# ProPrj_Sierra_Wireless_M2_Carrier_2026-0.net
KiCad netlist of a schematic drawn in EasyEDA Pro
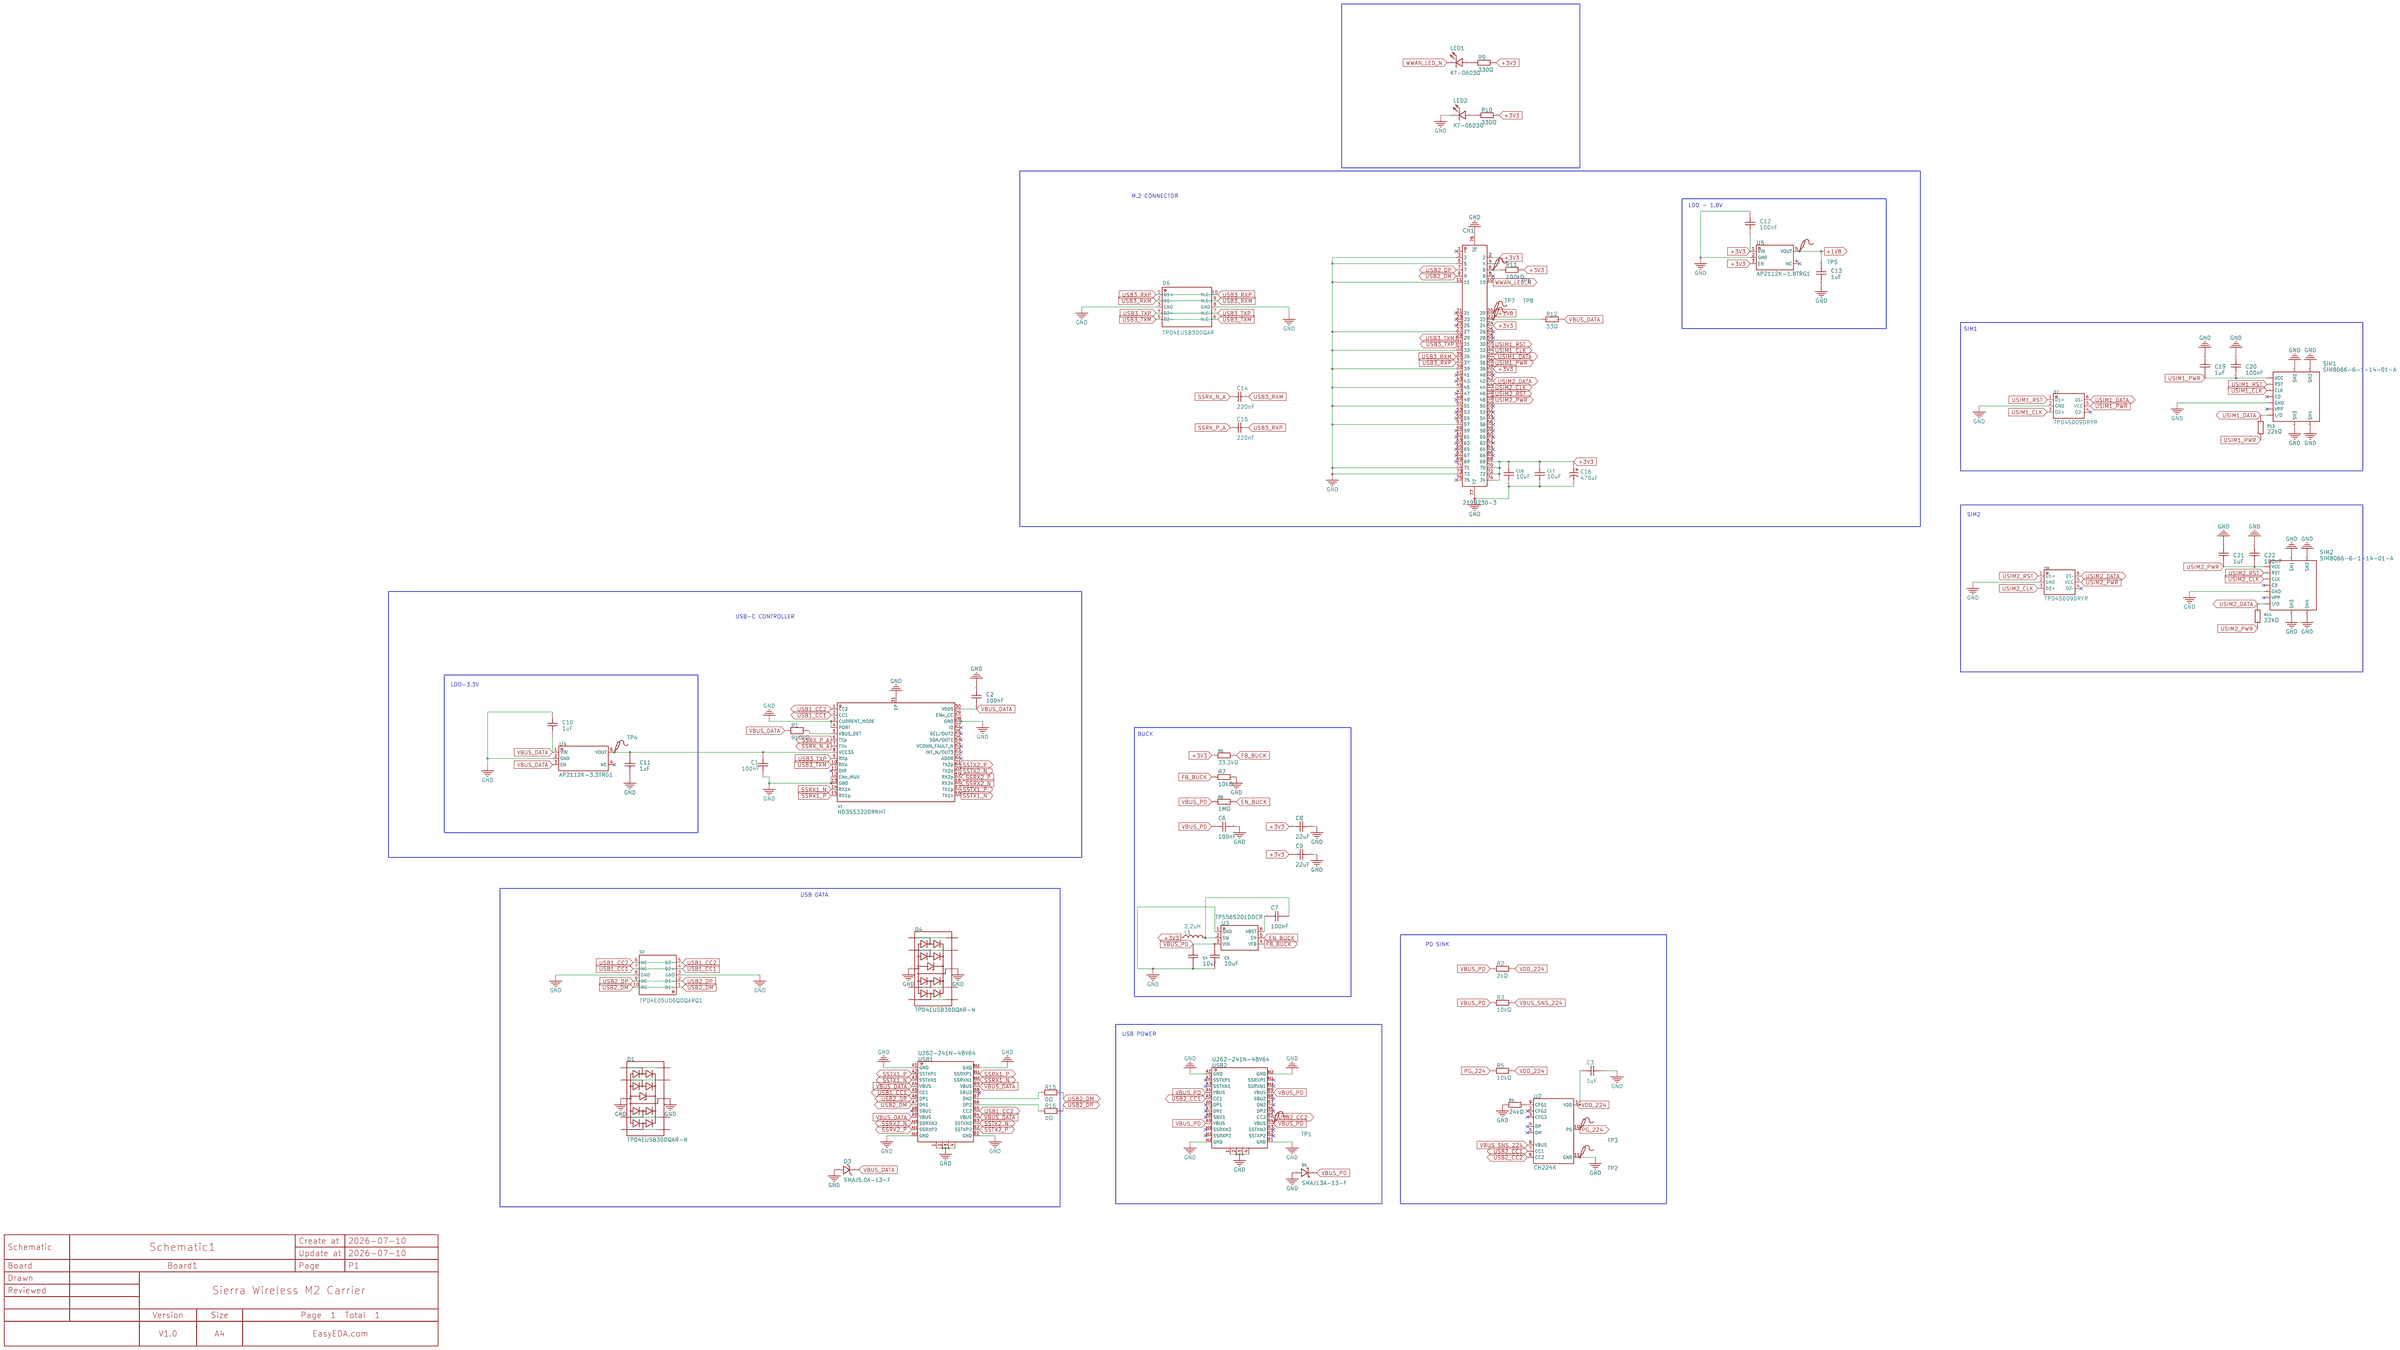
[diagram p0: schematic sheet]

(export (version "E")
  (design (tool "Eeschema 10.0.6"))
  (components
    (comp (ref "C1")
      (value "100nF")
      (footprint "easyedapro:C0603")
      (libsource (lib "easyedapro") (part "CAP"))
    )
    (comp (ref "C2")
      (value "100nF")
      (footprint "easyedapro:C0603")
      (libsource (lib "easyedapro") (part "CAP"))
    )
    (comp (ref "C3")
      (value "1uF")
      (footprint "easyedapro:C0603")
      (description "Capacitance:1uF Tolerance:±10% Tolerance:±10% Voltage Rating:50V Temperature Coefficient:X5R")
      (fields
        (field (name "Manufacturer Part") "CL10A105KB8NNNC")
        (field (name "Manufacturer") "SAMSUNG(三星)")
      )
      (libsource (lib "easyedapro") (part "CL10A105KB8NNNC"))
    )
    (comp (ref "C4")
      (value "10uF")
      (footprint "easyedapro:C0603")
      (description "Capacitance:10uF Tolerance:±20% Tolerance:±20% Voltage Rating:25V Temperature Coefficient:X5R")
      (fields
        (field (name "Manufacturer Part") "CL10A106MA8NRNC")
        (field (name "Manufacturer") "SAMSUNG(三星)")
      )
      (libsource (lib "easyedapro") (part "CL10A106MA8NRNC"))
    )
    (comp (ref "C5")
      (value "10uF")
      (footprint "easyedapro:C0603")
      (description "Capacitance:10uF Tolerance:±20% Tolerance:±20% Voltage Rating:25V Temperature Coefficient:X5R")
      (fields
        (field (name "Manufacturer Part") "CL10A106MA8NRNC")
        (field (name "Manufacturer") "SAMSUNG(三星)")
      )
      (libsource (lib "easyedapro") (part "CL10A106MA8NRNC"))
    )
    (comp (ref "C6")
      (value "100nF")
      (footprint "easyedapro:C0402")
      (description "Capacitance:100nF Tolerance:±10% Tolerance:±10% Voltage Rating:50V Temperature Coefficient:X7R")
      (fields
        (field (name "Manufacturer Part") "CL05B104KB54PNC")
        (field (name "Manufacturer") "SAMSUNG(三星)")
      )
      (libsource (lib "easyedapro") (part "CL05B104KB54PNC"))
    )
    (comp (ref "C7")
      (value "100nF")
      (footprint "easyedapro:C0402")
      (description "Capacitance:100nF Tolerance:±10% Tolerance:±10% Voltage Rating:50V Temperature Coefficient:X7R")
      (fields
        (field (name "Manufacturer Part") "CL05B104KB54PNC")
        (field (name "Manufacturer") "SAMSUNG(三星)")
      )
      (libsource (lib "easyedapro") (part "CL05B104KB54PNC"))
    )
    (comp (ref "C8")
      (value "22uF")
      (footprint "easyedapro:C0603")
      (description "Capacitance:22uF Tolerance:±20% Tolerance:±20% Voltage Rating:10V Temperature Coefficient:X5R")
      (fields
        (field (name "Manufacturer Part") "CL10A226MP8NUNE")
        (field (name "Manufacturer") "SAMSUNG(三星)")
      )
      (libsource (lib "easyedapro") (part "CL10A226MP8NUNE"))
    )
    (comp (ref "C9")
      (value "22uF")
      (footprint "easyedapro:C0603")
      (description "Capacitance:22uF Tolerance:±20% Tolerance:±20% Voltage Rating:10V Temperature Coefficient:X5R")
      (fields
        (field (name "Manufacturer Part") "CL10A226MP8NUNE")
        (field (name "Manufacturer") "SAMSUNG(三星)")
      )
      (libsource (lib "easyedapro") (part "CL10A226MP8NUNE"))
    )
    (comp (ref "C10")
      (value "1uF")
      (footprint "easyedapro:C0603")
      (description "Capacitance:1uF Tolerance:±10% Tolerance:±10% Voltage Rating:50V Temperature Coefficient:X5R")
      (fields
        (field (name "Manufacturer Part") "CL10A105KB8NNNC")
        (field (name "Manufacturer") "SAMSUNG(三星)")
      )
      (libsource (lib "easyedapro") (part "CL10A105KB8NNNC"))
    )
    (comp (ref "C11")
      (value "1uF")
      (footprint "easyedapro:C0603")
      (description "Capacitance:1uF Tolerance:±10% Tolerance:±10% Voltage Rating:50V Temperature Coefficient:X5R")
      (fields
        (field (name "Manufacturer Part") "CL10A105KB8NNNC")
        (field (name "Manufacturer") "SAMSUNG(三星)")
      )
      (libsource (lib "easyedapro") (part "CL10A105KB8NNNC"))
    )
    (comp (ref "C12")
      (value "100nF")
      (footprint "easyedapro:C0402")
      (description "Capacitance:100nF Tolerance:±10% Tolerance:±10% Voltage Rating:50V Temperature Coefficient:X7R")
      (fields
        (field (name "Manufacturer Part") "CL05B104KB54PNC")
        (field (name "Manufacturer") "SAMSUNG(三星)")
      )
      (libsource (lib "easyedapro") (part "CL05B104KB54PNC"))
    )
    (comp (ref "C13")
      (value "1uF")
      (footprint "easyedapro:C0603")
      (description "Capacitance:1uF Tolerance:±10% Tolerance:±10% Voltage Rating:50V Temperature Coefficient:X5R")
      (fields
        (field (name "Manufacturer Part") "CL10A105KB8NNNC")
        (field (name "Manufacturer") "SAMSUNG(三星)")
      )
      (libsource (lib "easyedapro") (part "CL10A105KB8NNNC"))
    )
    (comp (ref "C14")
      (value "220nF")
      (footprint "easyedapro:C0603")
      (description "Capacitance:220nF Tolerance:±10% Tolerance:±10% Voltage Rating:50V Temperature Coefficient:X7R")
      (fields
        (field (name "Manufacturer Part") "CL10B224KB8NNNC")
        (field (name "Manufacturer") "SAMSUNG(三星)")
      )
      (libsource (lib "easyedapro") (part "CL10B224KB8NNNC"))
    )
    (comp (ref "C15")
      (value "220nF")
      (footprint "easyedapro:C0603")
      (description "Capacitance:220nF Tolerance:±10% Tolerance:±10% Voltage Rating:50V Temperature Coefficient:X7R")
      (fields
        (field (name "Manufacturer Part") "CL10B224KB8NNNC")
        (field (name "Manufacturer") "SAMSUNG(三星)")
      )
      (libsource (lib "easyedapro") (part "CL10B224KB8NNNC"))
    )
    (comp (ref "C16")
      (value "470uF")
      (footprint "easyedapro:CAP-TH_BD8.0-P3.50-D0.5-FD")
      (fields
        (field (name "Manufacturer Part") "03EC0575")
        (field (name "Manufacturer") "KNSCHA(科尼盛)")
        (field (name "Tolerance") "±20%")
      )
      (libsource (lib "easyedapro") (part "03EC0575"))
    )
    (comp (ref "C17")
      (value "10uF")
      (footprint "easyedapro:C0603")
      (description "Capacitance:10uF Tolerance:±20% Tolerance:±20% Voltage Rating:25V Temperature Coefficient:X5R")
      (fields
        (field (name "Manufacturer Part") "CL10A106MA8NRNC")
        (field (name "Manufacturer") "SAMSUNG(三星)")
      )
      (libsource (lib "easyedapro") (part "CL10A106MA8NRNC"))
    )
    (comp (ref "C18")
      (value "10uF")
      (footprint "easyedapro:C0603")
      (description "Capacitance:10uF Tolerance:±20% Tolerance:±20% Voltage Rating:25V Temperature Coefficient:X5R")
      (fields
        (field (name "Manufacturer Part") "CL10A106MA8NRNC")
        (field (name "Manufacturer") "SAMSUNG(三星)")
      )
      (libsource (lib "easyedapro") (part "CL10A106MA8NRNC"))
    )
    (comp (ref "C19")
      (value "1uF")
      (footprint "easyedapro:C0603")
      (description "Capacitance:1uF Tolerance:±10% Tolerance:±10% Voltage Rating:50V Temperature Coefficient:X5R")
      (fields
        (field (name "Manufacturer Part") "CL10A105KB8NNNC")
        (field (name "Manufacturer") "SAMSUNG(三星)")
      )
      (libsource (lib "easyedapro") (part "CL10A105KB8NNNC"))
    )
    (comp (ref "C20")
      (value "100nF")
      (footprint "easyedapro:C0402")
      (description "Capacitance:100nF Tolerance:±10% Tolerance:±10% Voltage Rating:50V Temperature Coefficient:X7R")
      (fields
        (field (name "Manufacturer Part") "CL05B104KB54PNC")
        (field (name "Manufacturer") "SAMSUNG(三星)")
      )
      (libsource (lib "easyedapro") (part "CL05B104KB54PNC"))
    )
    (comp (ref "C21")
      (value "1uF")
      (footprint "easyedapro:C0603")
      (description "Capacitance:1uF Tolerance:±10% Tolerance:±10% Voltage Rating:50V Temperature Coefficient:X5R")
      (fields
        (field (name "Manufacturer Part") "CL10A105KB8NNNC")
        (field (name "Manufacturer") "SAMSUNG(三星)")
      )
      (libsource (lib "easyedapro") (part "CL10A105KB8NNNC"))
    )
    (comp (ref "C22")
      (value "100nF")
      (footprint "easyedapro:C0402")
      (description "Capacitance:100nF Tolerance:±10% Tolerance:±10% Voltage Rating:50V Temperature Coefficient:X7R")
      (fields
        (field (name "Manufacturer Part") "CL05B104KB54PNC")
        (field (name "Manufacturer") "SAMSUNG(三星)")
      )
      (libsource (lib "easyedapro") (part "CL05B104KB54PNC"))
    )
    (comp (ref "CN1")
      (value "2199230-3")
      (footprint "easyedapro:PCIE-SMD_2199230-3_1")
      (fields (field (name "Manufacturer") "TE Connectivity(泰科电子)"))
      (libsource (lib "easyedapro") (part "2199230-3"))
    )
    (comp (ref "D1")
      (value "TPD4EUSB30DQAR-N")
      (footprint "easyedapro:DFN-10_L2.5-W1.0-P0.50-BL-A")
      (fields (field (name "Manufacturer") "BORN(伯恩半导体)"))
      (libsource (lib "easyedapro") (part "TPD4EUSB30DQAR-N"))
    )
    (comp (ref "D2")
      (value "TPD4E05U06QDQARQ1")
      (footprint "easyedapro:USON-10_L2.5-W1.0-P0.50-BL")
      (fields (field (name "Manufacturer") "TI(德州仪器)"))
      (libsource (lib "easyedapro") (part "TPD4E05U06QDQARQ1"))
    )
    (comp (ref "D3")
      (value "SMAJ5.0A-13-F")
      (footprint "easyedapro:SMA_L4.3-W2.6-LS5.2-RD")
      (fields (field (name "Manufacturer") "DIODES(美台)"))
      (libsource (lib "easyedapro") (part "SMAJ5.0A-13-F"))
    )
    (comp (ref "D4")
      (value "TPD4EUSB30DQAR-N")
      (footprint "easyedapro:DFN-10_L2.5-W1.0-P0.50-BL-A")
      (fields (field (name "Manufacturer") "BORN(伯恩半导体)"))
      (libsource (lib "easyedapro") (part "TPD4EUSB30DQAR-N"))
    )
    (comp (ref "D5")
      (value "SMAJ13A-13-F")
      (footprint "easyedapro:SMA_L4.4-W2.6-LS5.0-RD")
      (fields (field (name "Manufacturer") "DIODES(美台)"))
      (libsource (lib "easyedapro") (part "SMAJ13A-13-F"))
    )
    (comp (ref "D6")
      (value "TPD4EUSB30DQAR")
      (footprint "easyedapro:USON-10_L2.5-W1.0-P0.50-BL")
      (fields (field (name "Manufacturer") "TI(德州仪器)"))
      (libsource (lib "easyedapro") (part "TPD4EUSB30DQAR"))
    )
    (comp (ref "D7")
      (value "TPD4S009DRYR")
      (footprint "easyedapro:SON-6_L1.5-W1.0-P0.50-TL")
      (fields (field (name "Manufacturer") "TI(德州仪器)"))
      (libsource (lib "easyedapro") (part "TPD4S009DRYR"))
    )
    (comp (ref "D8")
      (value "TPD4S009DRYR")
      (footprint "easyedapro:SON-6_L1.5-W1.0-P0.50-TL")
      (fields (field (name "Manufacturer") "TI(德州仪器)"))
      (libsource (lib "easyedapro") (part "TPD4S009DRYR"))
    )
    (comp (ref "L1")
      (value "2.2uH")
      (footprint "easyedapro:IND-SMD_L4.0-W4.0_YHNR4020")
      (fields (field (name "Manufacturer Part") "YHNR4020-2R2M") (field (name "Manufacturer") "YJYCOIN(益嘉源)"))
      (libsource (lib "easyedapro") (part "YHNR4020-2R2M"))
    )
    (comp (ref "LED1")
      (value "KT-0603G")
      (footprint "easyedapro:LED0603-RD")
      (fields (field (name "Manufacturer") "KENTO"))
      (libsource (lib "easyedapro") (part "0603 Green 509-620mcd"))
    )
    (comp (ref "LED2")
      (value "KT-0603G")
      (footprint "easyedapro:LED0603-RD")
      (fields (field (name "Manufacturer") "KENTO"))
      (libsource (lib "easyedapro") (part "0603 Green 509-620mcd"))
    )
    (comp (ref "R1")
      (value "910kΩ")
      (footprint "easyedapro:R0402")
      (fields
        (field (name "Manufacturer Part") "FRC0402F9103TS")
        (field (name "Manufacturer") "FOJAN(富捷)")
        (field (name "Tolerance") "±1%")
      )
      (libsource (lib "easyedapro") (part "FRC0402F9103TS"))
    )
    (comp (ref "R2")
      (value "2kΩ")
      (footprint "easyedapro:R0805")
      (fields
        (field (name "Manufacturer Part") "0805W8J0202T5E")
        (field (name "Manufacturer") "UNI-ROYAL(厚声)")
        (field (name "Tolerance") "±5%")
      )
      (libsource (lib "easyedapro") (part "0805W8J0202T5E"))
    )
    (comp (ref "R3")
      (value "10kΩ")
      (footprint "easyedapro:R0603")
      (fields
        (field (name "Manufacturer Part") "RC0603FR-0710KL")
        (field (name "Manufacturer") "YAGEO(国巨)")
        (field (name "Tolerance") "±1%")
      )
      (libsource (lib "easyedapro") (part "RC0603FR-0710KL"))
    )
    (comp (ref "R4")
      (value "24kΩ")
      (footprint "easyedapro:R0603")
      (fields
        (field (name "Manufacturer Part") "0603WAF2402T5E")
        (field (name "Manufacturer") "UNI-ROYAL(厚声)")
        (field (name "Tolerance") "±1%")
      )
      (libsource (lib "easyedapro") (part "0603WAF2402T5E"))
    )
    (comp (ref "R5")
      (value "10kΩ")
      (footprint "easyedapro:R0603")
      (fields
        (field (name "Manufacturer Part") "RC0603FR-0710KL")
        (field (name "Manufacturer") "YAGEO(国巨)")
        (field (name "Tolerance") "±1%")
      )
      (libsource (lib "easyedapro") (part "RC0603FR-0710KL"))
    )
    (comp (ref "R6")
      (value "33.2kΩ")
      (footprint "easyedapro:R0603")
      (fields
        (field (name "Manufacturer Part") "RMC060333.2K1%N")
        (field (name "Manufacturer") "Tyohm(幸亚电阻)")
        (field (name "Tolerance") "±1%")
      )
      (libsource (lib "easyedapro") (part "RMC060333.2K1%N"))
    )
    (comp (ref "R7")
      (value "10kΩ")
      (footprint "easyedapro:R0603")
      (fields
        (field (name "Manufacturer Part") "RC0603FR-0710KL")
        (field (name "Manufacturer") "YAGEO(国巨)")
        (field (name "Tolerance") "±1%")
      )
      (libsource (lib "easyedapro") (part "RC0603FR-0710KL"))
    )
    (comp (ref "R8")
      (value "1MΩ")
      (footprint "easyedapro:R0603")
      (fields
        (field (name "Manufacturer Part") "0603WAF1004T5E")
        (field (name "Manufacturer") "UNI-ROYAL(厚声)")
        (field (name "Tolerance") "±1%")
      )
      (libsource (lib "easyedapro") (part "0603WAF1004T5E"))
    )
    (comp (ref "R9")
      (value "330Ω")
      (footprint "easyedapro:R0603")
      (fields
        (field (name "Manufacturer Part") "0603WAF3300T5E")
        (field (name "Manufacturer") "UNI-ROYAL(厚声)")
        (field (name "Tolerance") "±1%")
      )
      (libsource (lib "easyedapro") (part "0603WAF3300T5E"))
    )
    (comp (ref "R10")
      (value "330Ω")
      (footprint "easyedapro:R0603")
      (fields
        (field (name "Manufacturer Part") "0603WAF3300T5E")
        (field (name "Manufacturer") "UNI-ROYAL(厚声)")
        (field (name "Tolerance") "±1%")
      )
      (libsource (lib "easyedapro") (part "0603WAF3300T5E"))
    )
    (comp (ref "R11")
      (value "100kΩ")
      (footprint "easyedapro:R0603")
      (fields
        (field (name "Manufacturer Part") "0603WAF1003T5E")
        (field (name "Manufacturer") "UNI-ROYAL(厚声)")
        (field (name "Tolerance") "±1%")
      )
      (libsource (lib "easyedapro") (part "0603WAF1003T5E"))
    )
    (comp (ref "R12")
      (value "33Ω")
      (footprint "easyedapro:R0603")
      (fields
        (field (name "Manufacturer Part") "0603WAF330JT5E")
        (field (name "Manufacturer") "UNI-ROYAL(厚声)")
        (field (name "Tolerance") "±1%")
      )
      (libsource (lib "easyedapro") (part "0603WAF330JT5E"))
    )
    (comp (ref "R13")
      (value "22kΩ")
      (footprint "easyedapro:R0603")
      (fields
        (field (name "Manufacturer Part") "0603WAF2202T5E")
        (field (name "Manufacturer") "UNI-ROYAL(厚声)")
        (field (name "Tolerance") "±1%")
      )
      (libsource (lib "easyedapro") (part "0603WAF2202T5E"))
    )
    (comp (ref "R14")
      (value "22kΩ")
      (footprint "easyedapro:R0603")
      (fields
        (field (name "Manufacturer Part") "0603WAF2202T5E")
        (field (name "Manufacturer") "UNI-ROYAL(厚声)")
        (field (name "Tolerance") "±1%")
      )
      (libsource (lib "easyedapro") (part "0603WAF2202T5E"))
    )
    (comp (ref "R15")
      (value "0Ω")
      (footprint "easyedapro:R0603")
      (fields
        (field (name "Manufacturer Part") "RC0603JR-070RL")
        (field (name "Manufacturer") "YAGEO(国巨)")
        (field (name "Tolerance") "±5%")
      )
      (libsource (lib "easyedapro") (part "RC0603JR-070RL"))
    )
    (comp (ref "R16")
      (value "0Ω")
      (footprint "easyedapro:R0603")
      (fields
        (field (name "Manufacturer Part") "RC0603JR-070RL")
        (field (name "Manufacturer") "YAGEO(国巨)")
        (field (name "Tolerance") "±5%")
      )
      (libsource (lib "easyedapro") (part "RC0603JR-070RL"))
    )
    (comp (ref "SIM1")
      (value "SIM8066-6-1-14-01-A")
      (footprint "easyedapro:SIM-SMD_SIM8066-6-1-14-01-A")
      (fields (field (name "Manufacturer") "GCT"))
      (libsource (lib "easyedapro") (part "SIM8066-6-1-14-01-A"))
    )
    (comp (ref "SIM2")
      (value "SIM8066-6-1-14-01-A")
      (footprint "easyedapro:SIM-SMD_SIM8066-6-1-14-01-A")
      (fields (field (name "Manufacturer") "GCT"))
      (libsource (lib "easyedapro") (part "SIM8066-6-1-14-01-A"))
    )
    (comp (ref "TP1")
      (value "~")
      (footprint "easyedapro:Test-Point-0.5mm")
      (libsource (lib "easyedapro") (part "Test-Point"))
    )
    (comp (ref "TP2")
      (value "~")
      (footprint "easyedapro:Test-Point-0.5mm")
      (libsource (lib "easyedapro") (part "Test-Point"))
    )
    (comp (ref "TP3")
      (value "~")
      (footprint "easyedapro:Test-Point-0.5mm")
      (libsource (lib "easyedapro") (part "Test-Point"))
    )
    (comp (ref "TP4")
      (value "~")
      (footprint "easyedapro:Test-Point-0.5mm")
      (libsource (lib "easyedapro") (part "Test-Point"))
    )
    (comp (ref "TP5")
      (value "~")
      (footprint "easyedapro:Test-Point-0.5mm")
      (description "Test Point 测试点")
      (libsource (lib "easyedapro") (part "Test-Point"))
    )
    (comp (ref "TP6")
      (value "~")
      (footprint "easyedapro:Test-Point-0.5mm")
      (libsource (lib "easyedapro") (part "Test-Point"))
    )
    (comp (ref "TP7")
      (value "~")
      (footprint "easyedapro:Test-Point-0.5mm")
      (libsource (lib "easyedapro") (part "Test-Point"))
    )
    (comp (ref "TP8")
      (value "~")
      (footprint "easyedapro:Test-Point-0.5mm")
      (libsource (lib "easyedapro") (part "Test-Point"))
    )
    (comp (ref "U1")
      (value "HD3SS3220RNHT")
      (footprint "easyedapro:WQFN-30_L4.5-W2.5-P0.4-BL-EP")
      (fields (field (name "Manufacturer") "TI(德州仪器)"))
      (libsource (lib "easyedapro") (part "HD3SS3220RNHT"))
    )
    (comp (ref "U2")
      (value "CH224K")
      (footprint "easyedapro:ESSOP-10_L4.9-W3.9-P1.0-LS6.0-TL-EP")
      (fields (field (name "Manufacturer") "WCH(南京沁恒)"))
      (libsource (lib "easyedapro") (part "CH224K"))
    )
    (comp (ref "U3")
      (value "TPS565201DDCR")
      (footprint "easyedapro:SOT-23-6_L2.9-W1.6-P0.95-LS2.8-BR")
      (fields (field (name "Manufacturer") "TI(德州仪器)"))
      (libsource (lib "easyedapro") (part "TPS565201DDCR"))
    )
    (comp (ref "U4")
      (value "AP2112K-3.3TRG1")
      (footprint "easyedapro:SOT-25-5_L2.9-W1.6-P0.95-LS2.8-BL")
      (fields (field (name "Manufacturer") "DIODES(美台)"))
      (libsource (lib "easyedapro") (part "AP2112K-3.3TRG1"))
    )
    (comp (ref "U5")
      (value "AP2112K-1.8TRG1")
      (footprint "easyedapro:SOT-25_L3.0-W1.6-P0.95-LS2.8-BL")
      (fields (field (name "Manufacturer") "DIODES(美台)"))
      (libsource (lib "easyedapro") (part "AP2112K-1.8TRG1"))
    )
    (comp (ref "USB1")
      (value "U262-241N-4BV64")
      (footprint "easyedapro:USB-C-SMD_TYC-324G")
      (fields (field (name "Manufacturer") "XKB Connection(中国星坤)"))
      (libsource (lib "easyedapro") (part "U262-241N-4BV64"))
    )
    (comp (ref "USB2")
      (value "U262-241N-4BV64")
      (footprint "easyedapro:USB-C-SMD_TYC-324G")
      (fields (field (name "Manufacturer") "XKB Connection(中国星坤)"))
      (libsource (lib "easyedapro") (part "U262-241N-4BV64"))
    )
  )
  (nets
    (net (code "1") (name "+1V8") (class "Default")
      (node (ref "C13") (pin "2") (pinfunction "2_2") (pintype "unspecified"))
      (node (ref "CN1") (pin "20") (pinfunction "20_20") (pintype "unspecified"))
      (node (ref "TP5") (pin "1") (pinfunction "1_1") (pintype "unspecified"))
      (node (ref "TP7") (pin "1") (pinfunction "1_1") (pintype "unspecified"))
      (node (ref "U5") (pin "5") (pinfunction "VOUT_5") (pintype "unspecified"))
    )
    (net (code "2") (name "+3V3") (class "Default")
      (node (ref "C12") (pin "1") (pinfunction "1_1") (pintype "input"))
      (node (ref "C16") (pin "1") (pinfunction "1_1") (pintype "input"))
      (node (ref "C17") (pin "1") (pinfunction "1_1") (pintype "input"))
      (node (ref "C18") (pin "1") (pinfunction "1_1") (pintype "input"))
      (node (ref "C8") (pin "1") (pinfunction "1_1") (pintype "unspecified"))
      (node (ref "C9") (pin "1") (pinfunction "1_1") (pintype "unspecified"))
      (node (ref "CN1") (pin "2") (pinfunction "2_2") (pintype "unspecified"))
      (node (ref "CN1") (pin "24") (pinfunction "24_24") (pintype "unspecified"))
      (node (ref "CN1") (pin "38") (pinfunction "38_38") (pintype "unspecified"))
      (node (ref "CN1") (pin "4") (pinfunction "4_4") (pintype "unspecified"))
      (node (ref "CN1") (pin "68") (pinfunction "68_68") (pintype "unspecified"))
      (node (ref "CN1") (pin "70") (pinfunction "70_70") (pintype "unspecified"))
      (node (ref "CN1") (pin "72") (pinfunction "72_72") (pintype "unspecified"))
      (node (ref "CN1") (pin "74") (pinfunction "74_74") (pintype "unspecified"))
      (node (ref "L1") (pin "1") (pinfunction "1_1") (pintype "unspecified"))
      (node (ref "R10") (pin "1") (pinfunction "1_1") (pintype "input"))
      (node (ref "R11") (pin "2") (pinfunction "2_2") (pintype "input"))
      (node (ref "R6") (pin "1") (pinfunction "1_1") (pintype "input"))
      (node (ref "R9") (pin "1") (pinfunction "1_1") (pintype "input"))
      (node (ref "U5") (pin "1") (pinfunction "VIN_1") (pintype "unspecified"))
      (node (ref "U5") (pin "3") (pinfunction "EN_3") (pintype "unspecified"))
    )
    (net (code "3") (name "EN_BUCK") (class "Default")
      (node (ref "R8") (pin "2") (pinfunction "2_2") (pintype "input"))
      (node (ref "U3") (pin "5") (pinfunction "EN_5") (pintype "unspecified"))
    )
    (net (code "4") (name "FB_BUCK") (class "Default")
      (node (ref "R6") (pin "2") (pinfunction "2_2") (pintype "input"))
      (node (ref "R7") (pin "1") (pinfunction "1_1") (pintype "input"))
      (node (ref "U3") (pin "4") (pinfunction "VFB_4") (pintype "unspecified"))
    )
    (net (code "5") (name "GND") (class "Default")
      (node (ref "C1") (pin "1") (pinfunction "1_1") (pintype "input"))
      (node (ref "C10") (pin "2") (pinfunction "2_2") (pintype "unspecified"))
      (node (ref "C11") (pin "1") (pinfunction "1_1") (pintype "unspecified"))
      (node (ref "C12") (pin "2") (pinfunction "2_2") (pintype "input"))
      (node (ref "C13") (pin "1") (pinfunction "1_1") (pintype "unspecified"))
      (node (ref "C16") (pin "2") (pinfunction "2_2") (pintype "input"))
      (node (ref "C17") (pin "2") (pinfunction "2_2") (pintype "input"))
      (node (ref "C18") (pin "2") (pinfunction "2_2") (pintype "input"))
      (node (ref "C19") (pin "1") (pinfunction "1_1") (pintype "unspecified"))
      (node (ref "C2") (pin "2") (pinfunction "2_2") (pintype "input"))
      (node (ref "C20") (pin "1") (pinfunction "1_1") (pintype "input"))
      (node (ref "C21") (pin "1") (pinfunction "1_1") (pintype "unspecified"))
      (node (ref "C22") (pin "1") (pinfunction "1_1") (pintype "input"))
      (node (ref "C3") (pin "2") (pinfunction "2_2") (pintype "unspecified"))
      (node (ref "C4") (pin "2") (pinfunction "2_2") (pintype "input"))
      (node (ref "C5") (pin "2") (pinfunction "2_2") (pintype "input"))
      (node (ref "C6") (pin "2") (pinfunction "2_2") (pintype "input"))
      (node (ref "C8") (pin "2") (pinfunction "2_2") (pintype "unspecified"))
      (node (ref "C9") (pin "2") (pinfunction "2_2") (pintype "unspecified"))
      (node (ref "CN1") (pin "11") (pinfunction "11_11") (pintype "unspecified"))
      (node (ref "CN1") (pin "27") (pinfunction "27_27") (pintype "unspecified"))
      (node (ref "CN1") (pin "3") (pinfunction "3_3") (pintype "unspecified"))
      (node (ref "CN1") (pin "33") (pinfunction "33_33") (pintype "unspecified"))
      (node (ref "CN1") (pin "39") (pinfunction "39_39") (pintype "unspecified"))
      (node (ref "CN1") (pin "45") (pinfunction "45_45") (pintype "unspecified"))
      (node (ref "CN1") (pin "5") (pinfunction "5_5") (pintype "unspecified"))
      (node (ref "CN1") (pin "51") (pinfunction "51_51") (pintype "unspecified"))
      (node (ref "CN1") (pin "57") (pinfunction "57_57") (pintype "unspecified"))
      (node (ref "CN1") (pin "71") (pinfunction "71_71") (pintype "unspecified"))
      (node (ref "CN1") (pin "73") (pinfunction "73_73") (pintype "unspecified"))
      (node (ref "CN1") (pin "76") (pinfunction "76_76") (pintype "unspecified"))
      (node (ref "CN1") (pin "77") (pinfunction "77_77") (pintype "unspecified"))
      (node (ref "D1") (pin "3") (pinfunction "3_3") (pintype "unspecified"))
      (node (ref "D1") (pin "8") (pinfunction "8_8") (pintype "unspecified"))
      (node (ref "D2") (pin "3") (pinfunction "GND_3") (pintype "input"))
      (node (ref "D2") (pin "8") (pinfunction "GND_8") (pintype "input"))
      (node (ref "D3") (pin "2") (pinfunction "A_2") (pintype "unspecified"))
      (node (ref "D4") (pin "3") (pinfunction "3_3") (pintype "unspecified"))
      (node (ref "D4") (pin "8") (pinfunction "8_8") (pintype "unspecified"))
      (node (ref "D5") (pin "2") (pinfunction "A_2") (pintype "input"))
      (node (ref "D6") (pin "3") (pinfunction "GND_3") (pintype "unspecified"))
      (node (ref "D6") (pin "8") (pinfunction "GND_8") (pintype "unspecified"))
      (node (ref "D7") (pin "2") (pinfunction "GND_2") (pintype "input"))
      (node (ref "D8") (pin "2") (pinfunction "GND_2") (pintype "input"))
      (node (ref "LED2") (pin "1") (pinfunction "K_1") (pintype "unspecified"))
      (node (ref "R4") (pin "1") (pinfunction "1_1") (pintype "input"))
      (node (ref "R7") (pin "2") (pinfunction "2_2") (pintype "input"))
      (node (ref "SIM1") (pin "5") (pinfunction "GND_5") (pintype "unspecified"))
      (node (ref "SIM1") (pin "SH1") (pinfunction "SH1_SH1") (pintype "unspecified"))
      (node (ref "SIM1") (pin "SH2") (pinfunction "SH2_SH2") (pintype "unspecified"))
      (node (ref "SIM1") (pin "SH3") (pinfunction "SH3_SH3") (pintype "unspecified"))
      (node (ref "SIM1") (pin "SH4") (pinfunction "SH4_SH4") (pintype "unspecified"))
      (node (ref "SIM2") (pin "5") (pinfunction "GND_5") (pintype "unspecified"))
      (node (ref "SIM2") (pin "SH1") (pinfunction "SH1_SH1") (pintype "unspecified"))
      (node (ref "SIM2") (pin "SH2") (pinfunction "SH2_SH2") (pintype "unspecified"))
      (node (ref "SIM2") (pin "SH3") (pinfunction "SH3_SH3") (pintype "unspecified"))
      (node (ref "SIM2") (pin "SH4") (pinfunction "SH4_SH4") (pintype "unspecified"))
      (node (ref "TP2") (pin "1") (pinfunction "1_1") (pintype "unspecified"))
      (node (ref "U1") (pin "12") (pinfunction "ENn_MUX_12") (pintype "input"))
      (node (ref "U1") (pin "13") (pinfunction "GND_13") (pintype "input"))
      (node (ref "U1") (pin "28") (pinfunction "GND_28") (pintype "input"))
      (node (ref "U1") (pin "29") (pinfunction "ENn_CC_29") (pintype "input"))
      (node (ref "U1") (pin "3") (pinfunction "CURRENT_MODE_3") (pintype "input"))
      (node (ref "U1") (pin "31") (pinfunction "EP_31") (pintype "input"))
      (node (ref "U1") (pin "4") (pinfunction "PORT_4") (pintype "input"))
      (node (ref "U2") (pin "11") (pinfunction "GND_11") (pintype "unspecified"))
      (node (ref "U3") (pin "1") (pinfunction "GND_1") (pintype "unspecified"))
      (node (ref "U4") (pin "2") (pinfunction "GND_2") (pintype "unspecified"))
      (node (ref "U5") (pin "2") (pinfunction "GND_2") (pintype "unspecified"))
      (node (ref "USB1") (pin "1") (pinfunction "1_1") (pintype "unspecified"))
      (node (ref "USB1") (pin "2") (pinfunction "2_2") (pintype "unspecified"))
      (node (ref "USB1") (pin "3") (pinfunction "3_3") (pintype "unspecified"))
      (node (ref "USB1") (pin "4") (pinfunction "4_4") (pintype "unspecified"))
      (node (ref "USB1") (pin "A1") (pinfunction "GND_A1") (pintype "unspecified"))
      (node (ref "USB1") (pin "A12") (pinfunction "GND_A12") (pintype "unspecified"))
      (node (ref "USB1") (pin "B1") (pinfunction "GND_B1") (pintype "unspecified"))
      (node (ref "USB1") (pin "B12") (pinfunction "GND_B12") (pintype "unspecified"))
      (node (ref "USB2") (pin "1") (pinfunction "1_1") (pintype "unspecified"))
      (node (ref "USB2") (pin "2") (pinfunction "2_2") (pintype "unspecified"))
      (node (ref "USB2") (pin "3") (pinfunction "3_3") (pintype "unspecified"))
      (node (ref "USB2") (pin "4") (pinfunction "4_4") (pintype "unspecified"))
      (node (ref "USB2") (pin "A1") (pinfunction "GND_A1") (pintype "unspecified"))
      (node (ref "USB2") (pin "A12") (pinfunction "GND_A12") (pintype "unspecified"))
      (node (ref "USB2") (pin "B1") (pinfunction "GND_B1") (pintype "unspecified"))
      (node (ref "USB2") (pin "B12") (pinfunction "GND_B12") (pintype "unspecified"))
    )
    (net (code "6") (name "Net-(CN1-Pad6)") (class "Default")
      (node (ref "CN1") (pin "6") (pinfunction "6_6") (pintype "unspecified"))
      (node (ref "R11") (pin "1") (pinfunction "1_1") (pintype "input"))
      (node (ref "TP6") (pin "1") (pinfunction "1_1") (pintype "unspecified"))
    )
    (net (code "7") (name "Net-(CN1-Pad22)") (class "Default")
      (node (ref "CN1") (pin "22") (pinfunction "22_22") (pintype "unspecified"))
      (node (ref "R12") (pin "1") (pinfunction "1_1") (pintype "input"))
      (node (ref "TP8") (pin "1") (pinfunction "1_1") (pintype "unspecified"))
    )
    (net (code "8") (name "Net-(D1-Pad1)") (class "Default")
      (node (ref "D1") (pin "1") (pinfunction "1_1") (pintype "unspecified"))
      (node (ref "D1") (pin "10") (pinfunction "10_10") (pintype "unspecified"))
    )
    (net (code "9") (name "Net-(D1-Pad2)") (class "Default")
      (node (ref "D1") (pin "2") (pinfunction "2_2") (pintype "unspecified"))
      (node (ref "D1") (pin "9") (pinfunction "9_9") (pintype "unspecified"))
    )
    (net (code "10") (name "Net-(D1-Pad4)") (class "Default")
      (node (ref "D1") (pin "4") (pinfunction "4_4") (pintype "unspecified"))
      (node (ref "D1") (pin "7") (pinfunction "7_7") (pintype "unspecified"))
    )
    (net (code "11") (name "Net-(D1-Pad5)") (class "Default")
      (node (ref "D1") (pin "5") (pinfunction "5_5") (pintype "unspecified"))
      (node (ref "D1") (pin "6") (pinfunction "6_6") (pintype "unspecified"))
    )
    (net (code "12") (name "Net-(D4-Pad1)") (class "Default")
      (node (ref "D4") (pin "1") (pinfunction "1_1") (pintype "unspecified"))
      (node (ref "D4") (pin "10") (pinfunction "10_10") (pintype "unspecified"))
    )
    (net (code "13") (name "Net-(D4-Pad2)") (class "Default")
      (node (ref "D4") (pin "2") (pinfunction "2_2") (pintype "unspecified"))
      (node (ref "D4") (pin "9") (pinfunction "9_9") (pintype "unspecified"))
    )
    (net (code "14") (name "Net-(D4-Pad4)") (class "Default")
      (node (ref "D4") (pin "4") (pinfunction "4_4") (pintype "unspecified"))
      (node (ref "D4") (pin "7") (pinfunction "7_7") (pintype "unspecified"))
    )
    (net (code "15") (name "Net-(D4-Pad5)") (class "Default")
      (node (ref "D4") (pin "5") (pinfunction "5_5") (pintype "unspecified"))
      (node (ref "D4") (pin "6") (pinfunction "6_6") (pintype "unspecified"))
    )
    (net (code "16") (name "Net-(LED1-A)") (class "Default")
      (node (ref "LED1") (pin "2") (pinfunction "A_2") (pintype "unspecified"))
      (node (ref "R9") (pin "2") (pinfunction "2_2") (pintype "input"))
    )
    (net (code "17") (name "Net-(LED2-A)") (class "Default")
      (node (ref "LED2") (pin "2") (pinfunction "A_2") (pintype "unspecified"))
      (node (ref "R10") (pin "2") (pinfunction "2_2") (pintype "input"))
    )
    (net (code "18") (name "Net-(U1-VBUS_DET)") (class "Default")
      (node (ref "R1") (pin "2") (pinfunction "2_2") (pintype "unspecified"))
      (node (ref "U1") (pin "5") (pinfunction "VBUS_DET_5") (pintype "input"))
    )
    (net (code "19") (name "Net-(U1-VCC33)") (class "Default")
      (node (ref "C1") (pin "2") (pinfunction "2_2") (pintype "input"))
      (node (ref "C11") (pin "2") (pinfunction "2_2") (pintype "unspecified"))
      (node (ref "TP4") (pin "1") (pinfunction "1_1") (pintype "unspecified"))
      (node (ref "U1") (pin "8") (pinfunction "VCC33_8") (pintype "input"))
      (node (ref "U4") (pin "5") (pinfunction "VOUT_5") (pintype "unspecified"))
    )
    (net (code "20") (name "Net-(U2-CFG1)") (class "Default")
      (node (ref "R4") (pin "2") (pinfunction "2_2") (pintype "input"))
      (node (ref "U2") (pin "9") (pinfunction "CFG1_9") (pintype "unspecified"))
    )
    (net (code "21") (name "Net-(U3-SW)") (class "Default")
      (node (ref "C7") (pin "1") (pinfunction "1_1") (pintype "input"))
      (node (ref "L1") (pin "2") (pinfunction "2_2") (pintype "unspecified"))
      (node (ref "U3") (pin "2") (pinfunction "SW_2") (pintype "unspecified"))
    )
    (net (code "22") (name "Net-(U3-VBST)") (class "Default")
      (node (ref "C7") (pin "2") (pinfunction "2_2") (pintype "input"))
      (node (ref "U3") (pin "6") (pinfunction "VBST_6") (pintype "unspecified"))
    )
    (net (code "23") (name "Net-(USB1-DN2)") (class "Default")
      (node (ref "R15") (pin "1") (pinfunction "1_1") (pintype "input"))
      (node (ref "USB1") (pin "B7") (pinfunction "DN2_B7") (pintype "unspecified"))
    )
    (net (code "24") (name "Net-(USB1-DP2)") (class "Default")
      (node (ref "R16") (pin "1") (pinfunction "1_1") (pintype "input"))
      (node (ref "USB1") (pin "B6") (pinfunction "DP2_B6") (pintype "unspecified"))
    )
    (net (code "25") (name "PG_224") (class "Default")
      (node (ref "R5") (pin "1") (pinfunction "1_1") (pintype "input"))
      (node (ref "TP3") (pin "1") (pinfunction "1_1") (pintype "unspecified"))
      (node (ref "U2") (pin "10") (pinfunction "PG_10") (pintype "unspecified"))
    )
    (net (code "26") (name "SSRX1_N") (class "Default")
      (node (ref "U1") (pin "14") (pinfunction "RX1n_14") (pintype "input"))
      (node (ref "USB1") (pin "B10") (pinfunction "SSRXN1_B10") (pintype "unspecified"))
    )
    (net (code "27") (name "SSRX1_P") (class "Default")
      (node (ref "U1") (pin "15") (pinfunction "RX1p_15") (pintype "input"))
      (node (ref "USB1") (pin "B11") (pinfunction "SSRXP1_B11") (pintype "unspecified"))
    )
    (net (code "28") (name "SSRX2_N") (class "Default")
      (node (ref "U1") (pin "18") (pinfunction "RX2n_18") (pintype "input"))
      (node (ref "USB1") (pin "A10") (pinfunction "SSRXN2_A10") (pintype "unspecified"))
    )
    (net (code "29") (name "SSRX2_P") (class "Default")
      (node (ref "U1") (pin "19") (pinfunction "RX2p_19") (pintype "input"))
      (node (ref "USB1") (pin "A11") (pinfunction "SSRXP2_A11") (pintype "unspecified"))
    )
    (net (code "30") (name "SSRX_N_A") (class "Default")
      (node (ref "C14") (pin "1") (pinfunction "1_1") (pintype "input"))
      (node (ref "U1") (pin "7") (pinfunction "TXn_7") (pintype "input"))
    )
    (net (code "31") (name "SSRX_P_A") (class "Default")
      (node (ref "C15") (pin "1") (pinfunction "1_1") (pintype "input"))
      (node (ref "U1") (pin "6") (pinfunction "TXp_6") (pintype "input"))
    )
    (net (code "32") (name "SSTX1_N") (class "Default")
      (node (ref "U1") (pin "16") (pinfunction "TX1n_16") (pintype "input"))
      (node (ref "USB1") (pin "A3") (pinfunction "SSTXN1_A3") (pintype "unspecified"))
    )
    (net (code "33") (name "SSTX1_P") (class "Default")
      (node (ref "U1") (pin "17") (pinfunction "TX1p_17") (pintype "input"))
      (node (ref "USB1") (pin "A2") (pinfunction "SSTXP1_A2") (pintype "unspecified"))
    )
    (net (code "34") (name "SSTX2_N") (class "Default")
      (node (ref "U1") (pin "20") (pinfunction "TX2n_20") (pintype "input"))
      (node (ref "USB1") (pin "B3") (pinfunction "SSTXN2_B3") (pintype "unspecified"))
    )
    (net (code "35") (name "SSTX2_P") (class "Default")
      (node (ref "U1") (pin "21") (pinfunction "TX2p_21") (pintype "input"))
      (node (ref "USB1") (pin "B2") (pinfunction "SSTXP2_B2") (pintype "unspecified"))
    )
    (net (code "36") (name "USB1_CC1") (class "Default")
      (node (ref "D2") (pin "4") (pinfunction "D2+_4") (pintype "input"))
      (node (ref "D2") (pin "7") (pinfunction "NC_7") (pintype "input"))
      (node (ref "U1") (pin "2") (pinfunction "CC1_2") (pintype "input"))
      (node (ref "USB1") (pin "A5") (pinfunction "CC1_A5") (pintype "unspecified"))
    )
    (net (code "37") (name "USB1_CC2") (class "Default")
      (node (ref "D2") (pin "5") (pinfunction "D2-_5") (pintype "input"))
      (node (ref "D2") (pin "6") (pinfunction "NC_6") (pintype "input"))
      (node (ref "U1") (pin "1") (pinfunction "CC2_1") (pintype "input"))
      (node (ref "USB1") (pin "B5") (pinfunction "CC2_B5") (pintype "unspecified"))
    )
    (net (code "38") (name "USB2_CC1") (class "Default")
      (node (ref "U2") (pin "7") (pinfunction "CC1_7") (pintype "unspecified"))
      (node (ref "USB2") (pin "A5") (pinfunction "CC1_A5") (pintype "unspecified"))
    )
    (net (code "39") (name "USB2_CC2") (class "Default")
      (node (ref "U2") (pin "6") (pinfunction "CC2_6") (pintype "unspecified"))
      (node (ref "USB2") (pin "B5") (pinfunction "CC2_B5") (pintype "unspecified"))
    )
    (net (code "40") (name "USB2_DM") (class "Default")
      (node (ref "CN1") (pin "9") (pinfunction "9_9") (pintype "unspecified"))
      (node (ref "D2") (pin "1") (pinfunction "D1+_1") (pintype "input"))
      (node (ref "D2") (pin "10") (pinfunction "NC_10") (pintype "input"))
      (node (ref "R15") (pin "2") (pinfunction "2_2") (pintype "input"))
      (node (ref "USB1") (pin "A7") (pinfunction "DN1_A7") (pintype "unspecified"))
    )
    (net (code "41") (name "USB2_DP") (class "Default")
      (node (ref "CN1") (pin "7") (pinfunction "7_7") (pintype "unspecified"))
      (node (ref "D2") (pin "2") (pinfunction "D1-_2") (pintype "input"))
      (node (ref "D2") (pin "9") (pinfunction "NC_9") (pintype "input"))
      (node (ref "R16") (pin "2") (pinfunction "2_2") (pintype "input"))
      (node (ref "USB1") (pin "A6") (pinfunction "DP1_A6") (pintype "unspecified"))
    )
    (net (code "42") (name "USB3_RXM") (class "Default")
      (node (ref "C14") (pin "2") (pinfunction "2_2") (pintype "input"))
      (node (ref "CN1") (pin "35") (pinfunction "35_35") (pintype "unspecified"))
      (node (ref "D6") (pin "2") (pinfunction "D1-_2") (pintype "unspecified"))
      (node (ref "D6") (pin "9") (pinfunction "N.C._9") (pintype "unspecified"))
    )
    (net (code "43") (name "USB3_RXP") (class "Default")
      (node (ref "C15") (pin "2") (pinfunction "2_2") (pintype "input"))
      (node (ref "CN1") (pin "37") (pinfunction "37_37") (pintype "unspecified"))
      (node (ref "D6") (pin "1") (pinfunction "D1+_1") (pintype "unspecified"))
      (node (ref "D6") (pin "10") (pinfunction "N.C._10") (pintype "unspecified"))
    )
    (net (code "44") (name "USB3_TXM") (class "Default")
      (node (ref "CN1") (pin "29") (pinfunction "29_29") (pintype "unspecified"))
      (node (ref "D6") (pin "5") (pinfunction "D2-_5") (pintype "unspecified"))
      (node (ref "D6") (pin "6") (pinfunction "N.C._6") (pintype "unspecified"))
      (node (ref "U1") (pin "10") (pinfunction "RXn_10") (pintype "input"))
    )
    (net (code "45") (name "USB3_TXP") (class "Default")
      (node (ref "CN1") (pin "31") (pinfunction "31_31") (pintype "unspecified"))
      (node (ref "D6") (pin "4") (pinfunction "D2+_4") (pintype "unspecified"))
      (node (ref "D6") (pin "7") (pinfunction "N.C._7") (pintype "unspecified"))
      (node (ref "U1") (pin "9") (pinfunction "RXp_9") (pintype "input"))
    )
    (net (code "46") (name "USIM1_CLK") (class "Default")
      (node (ref "CN1") (pin "32") (pinfunction "32_32") (pintype "unspecified"))
      (node (ref "D7") (pin "3") (pinfunction "D2+_3") (pintype "input"))
      (node (ref "SIM1") (pin "3") (pinfunction "CLK_3") (pintype "unspecified"))
    )
    (net (code "47") (name "USIM1_DATA") (class "Default")
      (node (ref "CN1") (pin "34") (pinfunction "34_34") (pintype "unspecified"))
      (node (ref "D7") (pin "6") (pinfunction "D1–_6") (pintype "input"))
      (node (ref "R13") (pin "2") (pinfunction "2_2") (pintype "input"))
      (node (ref "SIM1") (pin "7") (pinfunction "I/O_7") (pintype "unspecified"))
    )
    (net (code "48") (name "USIM1_PWR") (class "Default")
      (node (ref "C19") (pin "2") (pinfunction "2_2") (pintype "unspecified"))
      (node (ref "C20") (pin "2") (pinfunction "2_2") (pintype "input"))
      (node (ref "CN1") (pin "36") (pinfunction "36_36") (pintype "unspecified"))
      (node (ref "D7") (pin "5") (pinfunction "VCC_5") (pintype "input"))
      (node (ref "R13") (pin "1") (pinfunction "1_1") (pintype "input"))
      (node (ref "SIM1") (pin "1") (pinfunction "VCC_1") (pintype "unspecified"))
    )
    (net (code "49") (name "USIM1_RST") (class "Default")
      (node (ref "CN1") (pin "30") (pinfunction "30_30") (pintype "unspecified"))
      (node (ref "D7") (pin "1") (pinfunction "D1+_1") (pintype "input"))
      (node (ref "SIM1") (pin "2") (pinfunction "RST_2") (pintype "unspecified"))
    )
    (net (code "50") (name "USIM2_CLK") (class "Default")
      (node (ref "CN1") (pin "44") (pinfunction "44_44") (pintype "unspecified"))
      (node (ref "D8") (pin "3") (pinfunction "D2+_3") (pintype "input"))
      (node (ref "SIM2") (pin "3") (pinfunction "CLK_3") (pintype "unspecified"))
    )
    (net (code "51") (name "USIM2_DATA") (class "Default")
      (node (ref "CN1") (pin "42") (pinfunction "42_42") (pintype "unspecified"))
      (node (ref "D8") (pin "6") (pinfunction "D1–_6") (pintype "input"))
      (node (ref "R14") (pin "2") (pinfunction "2_2") (pintype "input"))
      (node (ref "SIM2") (pin "7") (pinfunction "I/O_7") (pintype "unspecified"))
    )
    (net (code "52") (name "USIM2_PWR") (class "Default")
      (node (ref "C21") (pin "2") (pinfunction "2_2") (pintype "unspecified"))
      (node (ref "C22") (pin "2") (pinfunction "2_2") (pintype "input"))
      (node (ref "CN1") (pin "48") (pinfunction "48_48") (pintype "unspecified"))
      (node (ref "D8") (pin "5") (pinfunction "VCC_5") (pintype "input"))
      (node (ref "R14") (pin "1") (pinfunction "1_1") (pintype "input"))
      (node (ref "SIM2") (pin "1") (pinfunction "VCC_1") (pintype "unspecified"))
    )
    (net (code "53") (name "USIM2_RST") (class "Default")
      (node (ref "CN1") (pin "46") (pinfunction "46_46") (pintype "unspecified"))
      (node (ref "D8") (pin "1") (pinfunction "D1+_1") (pintype "input"))
      (node (ref "SIM2") (pin "2") (pinfunction "RST_2") (pintype "unspecified"))
    )
    (net (code "54") (name "VBUS_DATA") (class "Default")
      (node (ref "C10") (pin "1") (pinfunction "1_1") (pintype "unspecified"))
      (node (ref "C2") (pin "1") (pinfunction "1_1") (pintype "input"))
      (node (ref "D3") (pin "1") (pinfunction "C_1") (pintype "unspecified"))
      (node (ref "R1") (pin "1") (pinfunction "1_1") (pintype "unspecified"))
      (node (ref "R12") (pin "2") (pinfunction "2_2") (pintype "input"))
      (node (ref "U1") (pin "30") (pinfunction "VDD5_30") (pintype "input"))
      (node (ref "U4") (pin "1") (pinfunction "VIN_1") (pintype "unspecified"))
      (node (ref "U4") (pin "3") (pinfunction "EN_3") (pintype "unspecified"))
      (node (ref "USB1") (pin "A4") (pinfunction "VBUS_A4") (pintype "unspecified"))
      (node (ref "USB1") (pin "A9") (pinfunction "VBUS_A9") (pintype "unspecified"))
      (node (ref "USB1") (pin "B4") (pinfunction "VBUS_B4") (pintype "unspecified"))
      (node (ref "USB1") (pin "B9") (pinfunction "VBUS_B9") (pintype "unspecified"))
    )
    (net (code "55") (name "VBUS_PD") (class "Default")
      (node (ref "C4") (pin "1") (pinfunction "1_1") (pintype "input"))
      (node (ref "C5") (pin "1") (pinfunction "1_1") (pintype "input"))
      (node (ref "C6") (pin "1") (pinfunction "1_1") (pintype "input"))
      (node (ref "D5") (pin "1") (pinfunction "K_1") (pintype "input"))
      (node (ref "R2") (pin "1") (pinfunction "1_1") (pintype "input"))
      (node (ref "R3") (pin "1") (pinfunction "1_1") (pintype "input"))
      (node (ref "R8") (pin "1") (pinfunction "1_1") (pintype "input"))
      (node (ref "TP1") (pin "1") (pinfunction "1_1") (pintype "unspecified"))
      (node (ref "U3") (pin "3") (pinfunction "VIN_3") (pintype "unspecified"))
      (node (ref "USB2") (pin "A4") (pinfunction "VBUS_A4") (pintype "unspecified"))
      (node (ref "USB2") (pin "A9") (pinfunction "VBUS_A9") (pintype "unspecified"))
      (node (ref "USB2") (pin "B4") (pinfunction "VBUS_B4") (pintype "unspecified"))
      (node (ref "USB2") (pin "B9") (pinfunction "VBUS_B9") (pintype "unspecified"))
    )
    (net (code "56") (name "VBUS_SNS_224") (class "Default")
      (node (ref "R3") (pin "2") (pinfunction "2_2") (pintype "input"))
      (node (ref "U2") (pin "8") (pinfunction "VBUS_8") (pintype "unspecified"))
    )
    (net (code "57") (name "VDD_224") (class "Default")
      (node (ref "C3") (pin "1") (pinfunction "1_1") (pintype "unspecified"))
      (node (ref "R2") (pin "2") (pinfunction "2_2") (pintype "input"))
      (node (ref "R5") (pin "2") (pinfunction "2_2") (pintype "input"))
      (node (ref "U2") (pin "1") (pinfunction "VDD_1") (pintype "unspecified"))
    )
    (net (code "58") (name "WWAN_LED_N") (class "Default")
      (node (ref "CN1") (pin "10") (pinfunction "10_10") (pintype "unspecified"))
      (node (ref "LED1") (pin "1") (pinfunction "K_1") (pintype "unspecified"))
    )
    (net (code "59") (name "unconnected-(CN1-Pad1)") (class "Default")
      (node (ref "CN1") (pin "1") (pinfunction "1_1") (pintype "unspecified+no_connect"))
    )
    (net (code "60") (name "unconnected-(CN1-Pad8)") (class "Default")
      (node (ref "CN1") (pin "8") (pinfunction "8_8") (pintype "unspecified+no_connect"))
    )
    (net (code "61") (name "unconnected-(CN1-Pad21)") (class "Default")
      (node (ref "CN1") (pin "21") (pinfunction "21_21") (pintype "unspecified+no_connect"))
    )
    (net (code "62") (name "unconnected-(CN1-Pad23)") (class "Default")
      (node (ref "CN1") (pin "23") (pinfunction "23_23") (pintype "unspecified+no_connect"))
    )
    (net (code "63") (name "unconnected-(CN1-Pad25)") (class "Default")
      (node (ref "CN1") (pin "25") (pinfunction "25_25") (pintype "unspecified+no_connect"))
    )
    (net (code "64") (name "unconnected-(CN1-Pad26)") (class "Default")
      (node (ref "CN1") (pin "26") (pinfunction "26_26") (pintype "unspecified+no_connect"))
    )
    (net (code "65") (name "unconnected-(CN1-Pad28)") (class "Default")
      (node (ref "CN1") (pin "28") (pinfunction "28_28") (pintype "unspecified+no_connect"))
    )
    (net (code "66") (name "unconnected-(CN1-Pad40)") (class "Default")
      (node (ref "CN1") (pin "40") (pinfunction "40_40") (pintype "unspecified+no_connect"))
    )
    (net (code "67") (name "unconnected-(CN1-Pad41)") (class "Default")
      (node (ref "CN1") (pin "41") (pinfunction "41_41") (pintype "unspecified+no_connect"))
    )
    (net (code "68") (name "unconnected-(CN1-Pad43)") (class "Default")
      (node (ref "CN1") (pin "43") (pinfunction "43_43") (pintype "unspecified+no_connect"))
    )
    (net (code "69") (name "unconnected-(CN1-Pad47)") (class "Default")
      (node (ref "CN1") (pin "47") (pinfunction "47_47") (pintype "unspecified+no_connect"))
    )
    (net (code "70") (name "unconnected-(CN1-Pad49)") (class "Default")
      (node (ref "CN1") (pin "49") (pinfunction "49_49") (pintype "unspecified+no_connect"))
    )
    (net (code "71") (name "unconnected-(CN1-Pad50)") (class "Default")
      (node (ref "CN1") (pin "50") (pinfunction "50_50") (pintype "unspecified+no_connect"))
    )
    (net (code "72") (name "unconnected-(CN1-Pad52)") (class "Default")
      (node (ref "CN1") (pin "52") (pinfunction "52_52") (pintype "unspecified+no_connect"))
    )
    (net (code "73") (name "unconnected-(CN1-Pad53)") (class "Default")
      (node (ref "CN1") (pin "53") (pinfunction "53_53") (pintype "unspecified+no_connect"))
    )
    (net (code "74") (name "unconnected-(CN1-Pad54)") (class "Default")
      (node (ref "CN1") (pin "54") (pinfunction "54_54") (pintype "unspecified+no_connect"))
    )
    (net (code "75") (name "unconnected-(CN1-Pad55)") (class "Default")
      (node (ref "CN1") (pin "55") (pinfunction "55_55") (pintype "unspecified+no_connect"))
    )
    (net (code "76") (name "unconnected-(CN1-Pad56)") (class "Default")
      (node (ref "CN1") (pin "56") (pinfunction "56_56") (pintype "unspecified+no_connect"))
    )
    (net (code "77") (name "unconnected-(CN1-Pad58)") (class "Default")
      (node (ref "CN1") (pin "58") (pinfunction "58_58") (pintype "unspecified+no_connect"))
    )
    (net (code "78") (name "unconnected-(CN1-Pad59)") (class "Default")
      (node (ref "CN1") (pin "59") (pinfunction "59_59") (pintype "unspecified+no_connect"))
    )
    (net (code "79") (name "unconnected-(CN1-Pad60)") (class "Default")
      (node (ref "CN1") (pin "60") (pinfunction "60_60") (pintype "unspecified+no_connect"))
    )
    (net (code "80") (name "unconnected-(CN1-Pad61)") (class "Default")
      (node (ref "CN1") (pin "61") (pinfunction "61_61") (pintype "unspecified+no_connect"))
    )
    (net (code "81") (name "unconnected-(CN1-Pad62)") (class "Default")
      (node (ref "CN1") (pin "62") (pinfunction "62_62") (pintype "unspecified+no_connect"))
    )
    (net (code "82") (name "unconnected-(CN1-Pad63)") (class "Default")
      (node (ref "CN1") (pin "63") (pinfunction "63_63") (pintype "unspecified+no_connect"))
    )
    (net (code "83") (name "unconnected-(CN1-Pad64)") (class "Default")
      (node (ref "CN1") (pin "64") (pinfunction "64_64") (pintype "unspecified+no_connect"))
    )
    (net (code "84") (name "unconnected-(CN1-Pad65)") (class "Default")
      (node (ref "CN1") (pin "65") (pinfunction "65_65") (pintype "unspecified+no_connect"))
    )
    (net (code "85") (name "unconnected-(CN1-Pad66)") (class "Default")
      (node (ref "CN1") (pin "66") (pinfunction "66_66") (pintype "unspecified+no_connect"))
    )
    (net (code "86") (name "unconnected-(CN1-Pad67)") (class "Default")
      (node (ref "CN1") (pin "67") (pinfunction "67_67") (pintype "unspecified+no_connect"))
    )
    (net (code "87") (name "unconnected-(CN1-Pad69)") (class "Default")
      (node (ref "CN1") (pin "69") (pinfunction "69_69") (pintype "unspecified+no_connect"))
    )
    (net (code "88") (name "unconnected-(CN1-Pad75)") (class "Default")
      (node (ref "CN1") (pin "75") (pinfunction "75_75") (pintype "unspecified+no_connect"))
    )
    (net (code "89") (name "unconnected-(D7-D2–-Pad4)") (class "Default")
      (node (ref "D7") (pin "4") (pinfunction "D2–_4") (pintype "input+no_connect"))
    )
    (net (code "90") (name "unconnected-(D8-D2–-Pad4)") (class "Default")
      (node (ref "D8") (pin "4") (pinfunction "D2–_4") (pintype "input+no_connect"))
    )
    (net (code "91") (name "unconnected-(SIM1-PadCD)") (class "Default")
      (node (ref "SIM1") (pin "CD") (pinfunction "CD_CD") (pintype "unspecified+no_connect"))
    )
    (net (code "92") (name "unconnected-(SIM1-VPP-Pad6)") (class "Default")
      (node (ref "SIM1") (pin "6") (pinfunction "VPP_6") (pintype "unspecified+no_connect"))
    )
    (net (code "93") (name "unconnected-(SIM2-PadCD)") (class "Default")
      (node (ref "SIM2") (pin "CD") (pinfunction "CD_CD") (pintype "unspecified+no_connect"))
    )
    (net (code "94") (name "unconnected-(SIM2-VPP-Pad6)") (class "Default")
      (node (ref "SIM2") (pin "6") (pinfunction "VPP_6") (pintype "unspecified+no_connect"))
    )
    (net (code "95") (name "unconnected-(U1-ADDR-Pad22)") (class "Default")
      (node (ref "U1") (pin "22") (pinfunction "ADDR_22") (pintype "input+no_connect"))
    )
    (net (code "96") (name "unconnected-(U1-DIR-Pad11)") (class "Default")
      (node (ref "U1") (pin "11") (pinfunction "DIR_11") (pintype "input+no_connect"))
    )
    (net (code "97") (name "unconnected-(U1-ID-Pad27)") (class "Default")
      (node (ref "U1") (pin "27") (pinfunction "ID_27") (pintype "input+no_connect"))
    )
    (net (code "98") (name "unconnected-(U1-INT_N{slash}OUT3-Pad23)") (class "Default")
      (node (ref "U1") (pin "23") (pinfunction "INT_N/OUT3_23") (pintype "input+no_connect"))
    )
    (net (code "99") (name "unconnected-(U1-SCL{slash}OUT2-Pad26)") (class "Default")
      (node (ref "U1") (pin "26") (pinfunction "SCL/OUT2_26") (pintype "input+no_connect"))
    )
    (net (code "100") (name "unconnected-(U1-SDA{slash}OUT1-Pad25)") (class "Default")
      (node (ref "U1") (pin "25") (pinfunction "SDA/OUT1_25") (pintype "input+no_connect"))
    )
    (net (code "101") (name "unconnected-(U1-VCONN_FAULT_N-Pad24)") (class "Default")
      (node (ref "U1") (pin "24") (pinfunction "VCONN_FAULT_N_24") (pintype "input+no_connect"))
    )
    (net (code "102") (name "unconnected-(U2-CFG2-Pad2)") (class "Default")
      (node (ref "U2") (pin "2") (pinfunction "CFG2_2") (pintype "unspecified+no_connect"))
    )
    (net (code "103") (name "unconnected-(U2-CFG3-Pad3)") (class "Default")
      (node (ref "U2") (pin "3") (pinfunction "CFG3_3") (pintype "unspecified+no_connect"))
    )
    (net (code "104") (name "unconnected-(U2-DM-Pad5)") (class "Default")
      (node (ref "U2") (pin "5") (pinfunction "DM_5") (pintype "unspecified+no_connect"))
    )
    (net (code "105") (name "unconnected-(U2-DP-Pad4)") (class "Default")
      (node (ref "U2") (pin "4") (pinfunction "DP_4") (pintype "unspecified+no_connect"))
    )
    (net (code "106") (name "unconnected-(U4-NC-Pad4)") (class "Default")
      (node (ref "U4") (pin "4") (pinfunction "NC_4") (pintype "unspecified+no_connect"))
    )
    (net (code "107") (name "unconnected-(U5-NC-Pad4)") (class "Default")
      (node (ref "U5") (pin "4") (pinfunction "NC_4") (pintype "unspecified+no_connect"))
    )
    (net (code "108") (name "unconnected-(USB1-SBU1-PadA8)") (class "Default")
      (node (ref "USB1") (pin "A8") (pinfunction "SBU1_A8") (pintype "unspecified+no_connect"))
    )
    (net (code "109") (name "unconnected-(USB1-SBU2-PadB8)") (class "Default")
      (node (ref "USB1") (pin "B8") (pinfunction "SBU2_B8") (pintype "unspecified+no_connect"))
    )
    (net (code "110") (name "unconnected-(USB2-DN1-PadA7)") (class "Default")
      (node (ref "USB2") (pin "A7") (pinfunction "DN1_A7") (pintype "unspecified+no_connect"))
    )
    (net (code "111") (name "unconnected-(USB2-DN2-PadB7)") (class "Default")
      (node (ref "USB2") (pin "B7") (pinfunction "DN2_B7") (pintype "unspecified+no_connect"))
    )
    (net (code "112") (name "unconnected-(USB2-DP1-PadA6)") (class "Default")
      (node (ref "USB2") (pin "A6") (pinfunction "DP1_A6") (pintype "unspecified+no_connect"))
    )
    (net (code "113") (name "unconnected-(USB2-DP2-PadB6)") (class "Default")
      (node (ref "USB2") (pin "B6") (pinfunction "DP2_B6") (pintype "unspecified+no_connect"))
    )
    (net (code "114") (name "unconnected-(USB2-SBU1-PadA8)") (class "Default")
      (node (ref "USB2") (pin "A8") (pinfunction "SBU1_A8") (pintype "unspecified+no_connect"))
    )
    (net (code "115") (name "unconnected-(USB2-SBU2-PadB8)") (class "Default")
      (node (ref "USB2") (pin "B8") (pinfunction "SBU2_B8") (pintype "unspecified+no_connect"))
    )
    (net (code "116") (name "unconnected-(USB2-SSRXN1-PadB10)") (class "Default")
      (node (ref "USB2") (pin "B10") (pinfunction "SSRXN1_B10") (pintype "unspecified+no_connect"))
    )
    (net (code "117") (name "unconnected-(USB2-SSRXN2-PadA10)") (class "Default")
      (node (ref "USB2") (pin "A10") (pinfunction "SSRXN2_A10") (pintype "unspecified+no_connect"))
    )
    (net (code "118") (name "unconnected-(USB2-SSRXP1-PadB11)") (class "Default")
      (node (ref "USB2") (pin "B11") (pinfunction "SSRXP1_B11") (pintype "unspecified+no_connect"))
    )
    (net (code "119") (name "unconnected-(USB2-SSRXP2-PadA11)") (class "Default")
      (node (ref "USB2") (pin "A11") (pinfunction "SSRXP2_A11") (pintype "unspecified+no_connect"))
    )
    (net (code "120") (name "unconnected-(USB2-SSTXN1-PadA3)") (class "Default")
      (node (ref "USB2") (pin "A3") (pinfunction "SSTXN1_A3") (pintype "unspecified+no_connect"))
    )
    (net (code "121") (name "unconnected-(USB2-SSTXN2-PadB3)") (class "Default")
      (node (ref "USB2") (pin "B3") (pinfunction "SSTXN2_B3") (pintype "unspecified+no_connect"))
    )
    (net (code "122") (name "unconnected-(USB2-SSTXP1-PadA2)") (class "Default")
      (node (ref "USB2") (pin "A2") (pinfunction "SSTXP1_A2") (pintype "unspecified+no_connect"))
    )
    (net (code "123") (name "unconnected-(USB2-SSTXP2-PadB2)") (class "Default")
      (node (ref "USB2") (pin "B2") (pinfunction "SSTXP2_B2") (pintype "unspecified+no_connect"))
    )
  )
)
